# 11_Temp.net
KiCad netlist of a schematic drawn in Altium Designer
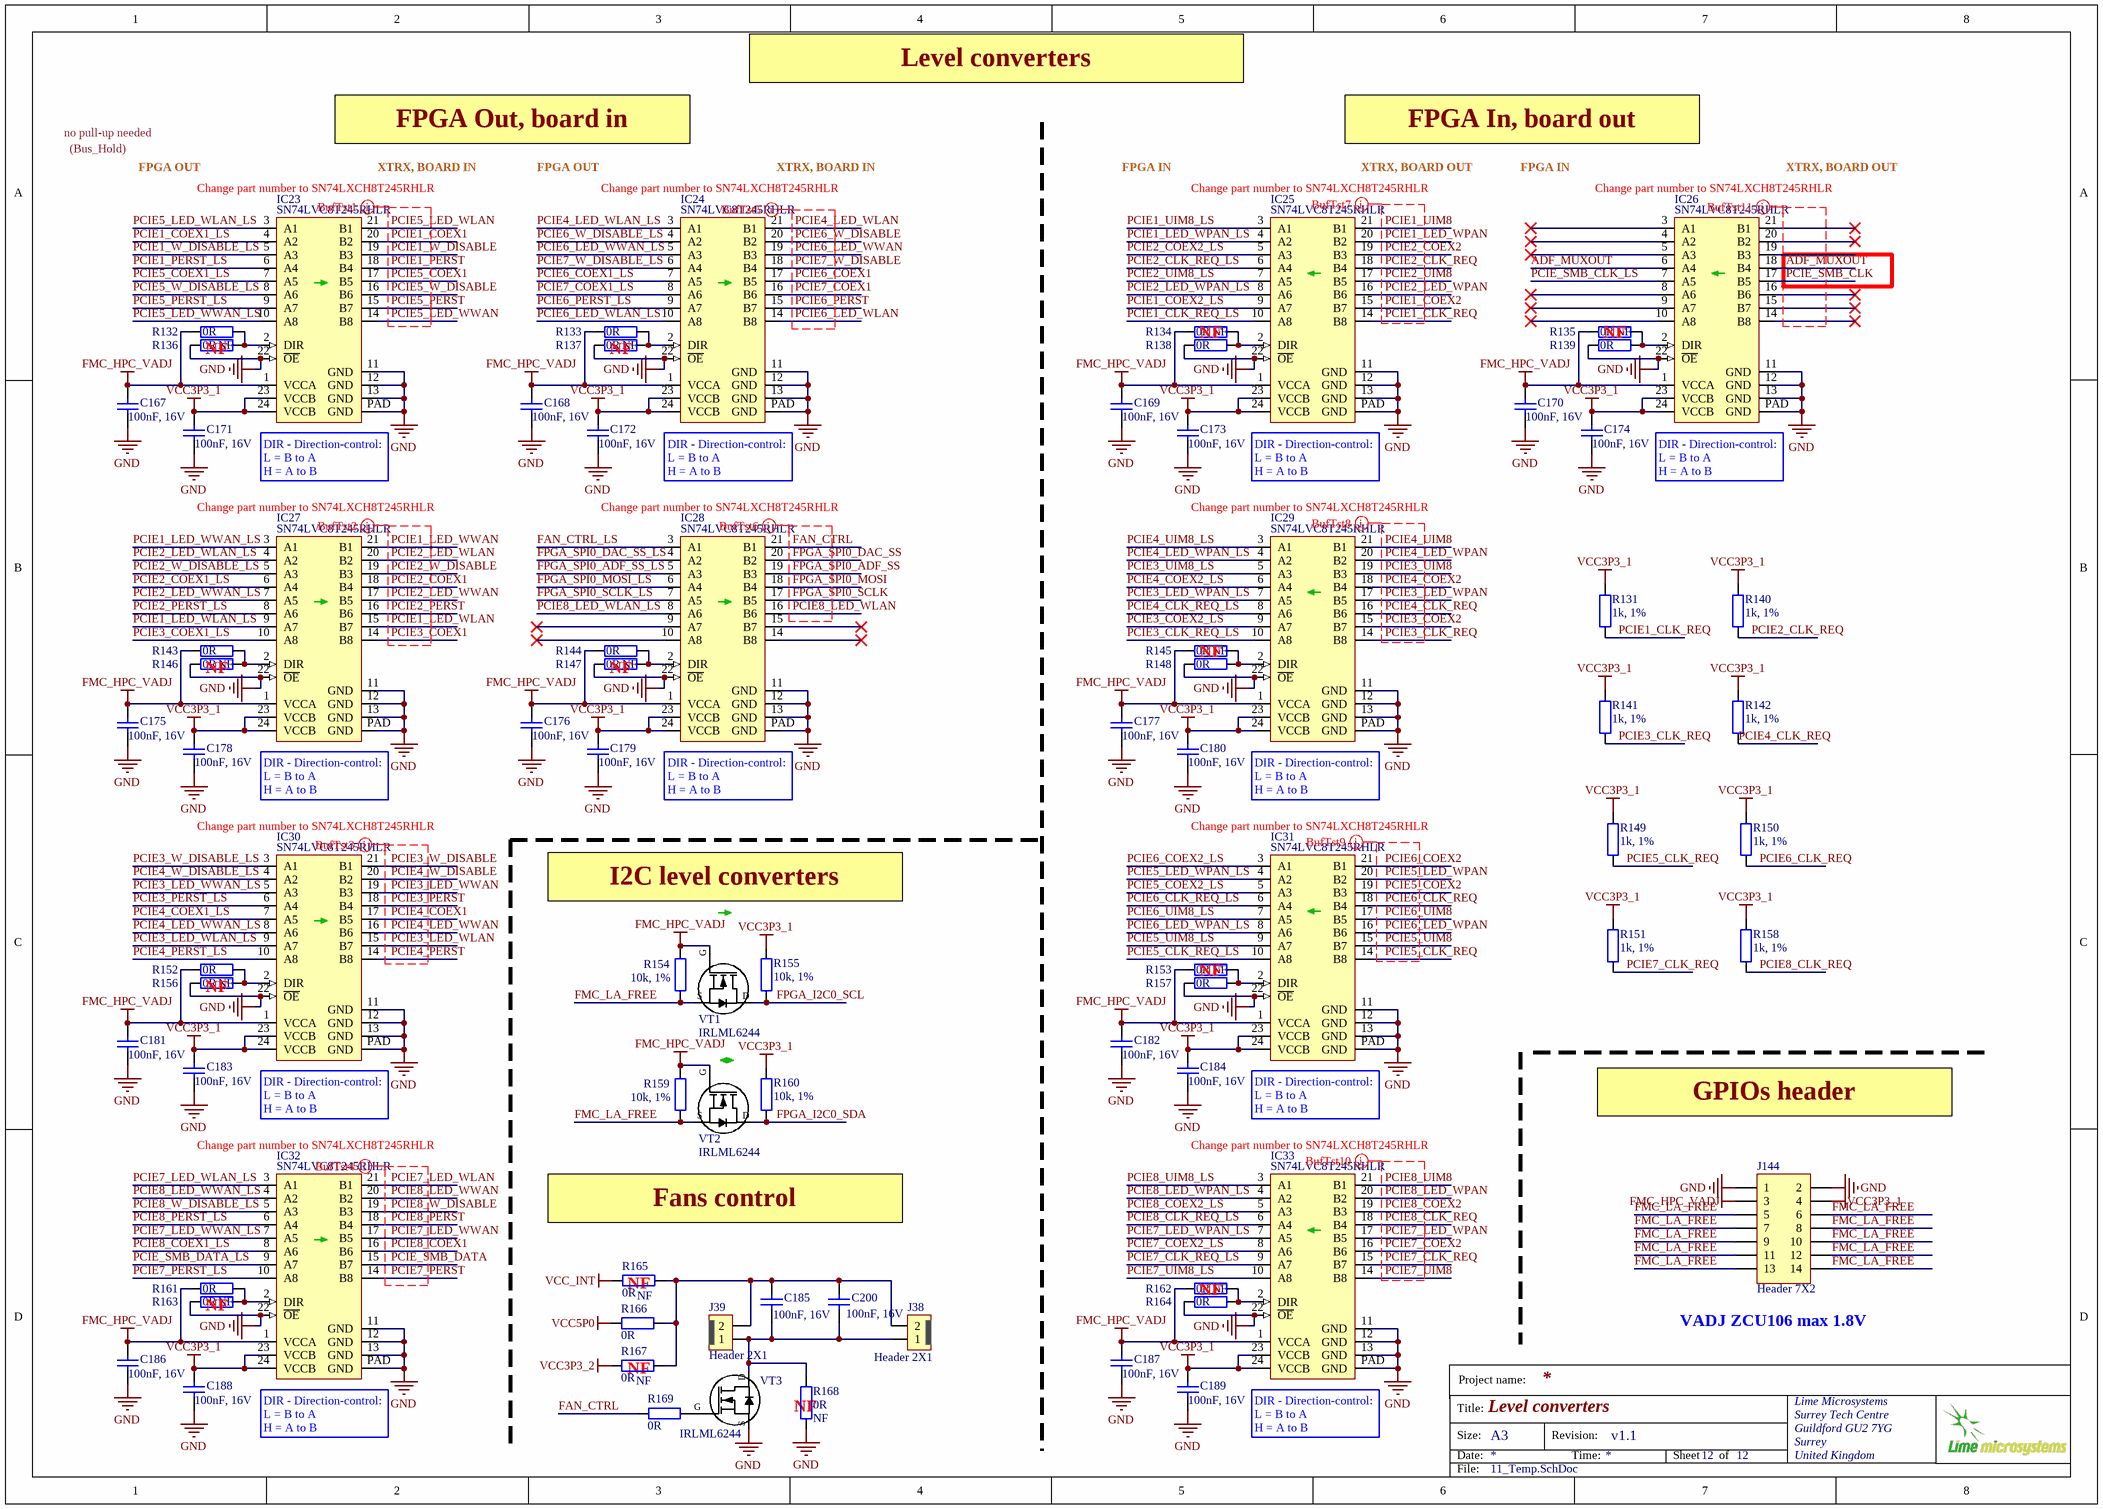
[diagram p0: 11_Temp.SchDoc]

(export (version "E")
  (design (tool "Eeschema 10.0.6"))
  (components
    (comp (ref "C167")
      (value "100nF, 16V")
      (footprint "CAP0402")
      (fields (field (name "TOLERANCE") "10 %") (field (name "MANUFACTURER") "Murata Electronics"))
      (libsource (lib "LimeFPGAboard_schLib") (part "Cap_0603"))
    )
    (comp (ref "C168")
      (value "100nF, 16V")
      (footprint "CAP0402")
      (fields (field (name "TOLERANCE") "10 %") (field (name "MANUFACTURER") "Murata Electronics"))
      (libsource (lib "LimeFPGAboard_schLib") (part "Cap_0603"))
    )
    (comp (ref "C169")
      (value "100nF, 16V")
      (footprint "CAP0402")
      (fields (field (name "TOLERANCE") "10 %") (field (name "MANUFACTURER") "Murata Electronics"))
      (libsource (lib "LimeFPGAboard_schLib") (part "Cap_0603"))
    )
    (comp (ref "C170")
      (value "100nF, 16V")
      (footprint "CAP0402")
      (fields (field (name "TOLERANCE") "10 %") (field (name "MANUFACTURER") "Murata Electronics"))
      (libsource (lib "LimeFPGAboard_schLib") (part "Cap_0603"))
    )
    (comp (ref "C171")
      (value "100nF, 16V")
      (footprint "CAP0402")
      (fields (field (name "TOLERANCE") "10 %") (field (name "MANUFACTURER") "Murata Electronics"))
      (libsource (lib "LimeFPGAboard_schLib") (part "Cap_0603"))
    )
    (comp (ref "C172")
      (value "100nF, 16V")
      (footprint "CAP0402")
      (fields (field (name "TOLERANCE") "10 %") (field (name "MANUFACTURER") "Murata Electronics"))
      (libsource (lib "LimeFPGAboard_schLib") (part "Cap_0603"))
    )
    (comp (ref "C173")
      (value "100nF, 16V")
      (footprint "CAP0402")
      (fields (field (name "TOLERANCE") "10 %") (field (name "MANUFACTURER") "Murata Electronics"))
      (libsource (lib "LimeFPGAboard_schLib") (part "Cap_0603"))
    )
    (comp (ref "C174")
      (value "100nF, 16V")
      (footprint "CAP0402")
      (fields (field (name "TOLERANCE") "10 %") (field (name "MANUFACTURER") "Murata Electronics"))
      (libsource (lib "LimeFPGAboard_schLib") (part "Cap_0603"))
    )
    (comp (ref "C175")
      (value "100nF, 16V")
      (footprint "CAP0402")
      (fields (field (name "TOLERANCE") "10 %") (field (name "MANUFACTURER") "Murata Electronics"))
      (libsource (lib "LimeFPGAboard_schLib") (part "Cap_0603"))
    )
    (comp (ref "C176")
      (value "100nF, 16V")
      (footprint "CAP0402")
      (fields (field (name "TOLERANCE") "10 %") (field (name "MANUFACTURER") "Murata Electronics"))
      (libsource (lib "LimeFPGAboard_schLib") (part "Cap_0603"))
    )
    (comp (ref "C177")
      (value "100nF, 16V")
      (footprint "CAP0402")
      (fields (field (name "TOLERANCE") "10 %") (field (name "MANUFACTURER") "Murata Electronics"))
      (libsource (lib "LimeFPGAboard_schLib") (part "Cap_0603"))
    )
    (comp (ref "C178")
      (value "100nF, 16V")
      (footprint "CAP0402")
      (fields (field (name "TOLERANCE") "10 %") (field (name "MANUFACTURER") "Murata Electronics"))
      (libsource (lib "LimeFPGAboard_schLib") (part "Cap_0603"))
    )
    (comp (ref "C179")
      (value "100nF, 16V")
      (footprint "CAP0402")
      (fields (field (name "TOLERANCE") "10 %") (field (name "MANUFACTURER") "Murata Electronics"))
      (libsource (lib "LimeFPGAboard_schLib") (part "Cap_0603"))
    )
    (comp (ref "C180")
      (value "100nF, 16V")
      (footprint "CAP0402")
      (fields (field (name "TOLERANCE") "10 %") (field (name "MANUFACTURER") "Murata Electronics"))
      (libsource (lib "LimeFPGAboard_schLib") (part "Cap_0603"))
    )
    (comp (ref "C181")
      (value "100nF, 16V")
      (footprint "CAP0402")
      (fields (field (name "TOLERANCE") "10 %") (field (name "MANUFACTURER") "Murata Electronics"))
      (libsource (lib "LimeFPGAboard_schLib") (part "Cap_0603"))
    )
    (comp (ref "C182")
      (value "100nF, 16V")
      (footprint "CAP0402")
      (fields (field (name "TOLERANCE") "10 %") (field (name "MANUFACTURER") "Murata Electronics"))
      (libsource (lib "LimeFPGAboard_schLib") (part "Cap_0603"))
    )
    (comp (ref "C183")
      (value "100nF, 16V")
      (footprint "CAP0402")
      (fields (field (name "TOLERANCE") "10 %") (field (name "MANUFACTURER") "Murata Electronics"))
      (libsource (lib "LimeFPGAboard_schLib") (part "Cap_0603"))
    )
    (comp (ref "C184")
      (value "100nF, 16V")
      (footprint "CAP0402")
      (fields (field (name "TOLERANCE") "10 %") (field (name "MANUFACTURER") "Murata Electronics"))
      (libsource (lib "LimeFPGAboard_schLib") (part "Cap_0603"))
    )
    (comp (ref "C185")
      (value "100nF, 16V")
      (footprint "CAP0402")
      (fields
        (field (name "TOLERANCE") "10 %")
        (field (name "MANUFACTURER") "Murata Electronics")
        (field (name "MANUFACTURER PART NUMBER") "GRM155R71C104KA88D")
      )
      (libsource (lib "") (part "Cap_0603_1"))
    )
    (comp (ref "C186")
      (value "100nF, 16V")
      (footprint "CAP0402")
      (fields (field (name "TOLERANCE") "10 %") (field (name "MANUFACTURER") "Murata Electronics"))
      (libsource (lib "LimeFPGAboard_schLib") (part "Cap_0603"))
    )
    (comp (ref "C187")
      (value "100nF, 16V")
      (footprint "CAP0402")
      (fields (field (name "TOLERANCE") "10 %") (field (name "MANUFACTURER") "Murata Electronics"))
      (libsource (lib "LimeFPGAboard_schLib") (part "Cap_0603"))
    )
    (comp (ref "C188")
      (value "100nF, 16V")
      (footprint "CAP0402")
      (fields (field (name "TOLERANCE") "10 %") (field (name "MANUFACTURER") "Murata Electronics"))
      (libsource (lib "LimeFPGAboard_schLib") (part "Cap_0603"))
    )
    (comp (ref "C189")
      (value "100nF, 16V")
      (footprint "CAP0402")
      (fields (field (name "TOLERANCE") "10 %") (field (name "MANUFACTURER") "Murata Electronics"))
      (libsource (lib "LimeFPGAboard_schLib") (part "Cap_0603"))
    )
    (comp (ref "C200")
      (value "100nF, 16V")
      (footprint "CAP0402")
      (fields
        (field (name "TOLERANCE") "10 %")
        (field (name "MANUFACTURER") "Murata Electronics")
        (field (name "MANUFACTURER PART NUMBER") "GRM155R71C104KA88D")
      )
      (libsource (lib "") (part "Cap_0603_1"))
    )
    (comp (ref "IC23")
      (value "SN74LVC8T245RHLR")
      (footprint "SN74LVC8T245RHLR_24-VQFN_LVL_SHIFTER")
      (fields (field (name "MANUFACTURER") "Texas Instruments"))
      (libsource (lib "*") (part "SN74LVC8T245RHLR_LVL_SHIFTER"))
    )
    (comp (ref "IC24")
      (value "SN74LVC8T245RHLR")
      (footprint "SN74LVC8T245RHLR_24-VQFN_LVL_SHIFTER")
      (fields (field (name "MANUFACTURER") "Texas Instruments"))
      (libsource (lib "*") (part "SN74LVC8T245RHLR_LVL_SHIFTER"))
    )
    (comp (ref "IC25")
      (value "SN74LVC8T245RHLR")
      (footprint "SN74LVC8T245RHLR_24-VQFN_LVL_SHIFTER")
      (fields (field (name "MANUFACTURER") "Texas Instruments"))
      (libsource (lib "*") (part "SN74LVC8T245RHLR_LVL_SHIFTER"))
    )
    (comp (ref "IC26")
      (value "SN74LVC8T245RHLR")
      (footprint "SN74LVC8T245RHLR_24-VQFN_LVL_SHIFTER")
      (fields (field (name "MANUFACTURER") "Texas Instruments"))
      (libsource (lib "*") (part "SN74LVC8T245RHLR_LVL_SHIFTER"))
    )
    (comp (ref "IC27")
      (value "SN74LVC8T245RHLR")
      (footprint "SN74LVC8T245RHLR_24-VQFN_LVL_SHIFTER")
      (fields (field (name "MANUFACTURER") "Texas Instruments"))
      (libsource (lib "*") (part "SN74LVC8T245RHLR_LVL_SHIFTER"))
    )
    (comp (ref "IC28")
      (value "SN74LVC8T245RHLR")
      (footprint "SN74LVC8T245RHLR_24-VQFN_LVL_SHIFTER")
      (fields (field (name "MANUFACTURER") "Texas Instruments"))
      (libsource (lib "*") (part "SN74LVC8T245RHLR_LVL_SHIFTER"))
    )
    (comp (ref "IC29")
      (value "SN74LVC8T245RHLR")
      (footprint "SN74LVC8T245RHLR_24-VQFN_LVL_SHIFTER")
      (fields (field (name "MANUFACTURER") "Texas Instruments"))
      (libsource (lib "*") (part "SN74LVC8T245RHLR_LVL_SHIFTER"))
    )
    (comp (ref "IC30")
      (value "SN74LVC8T245RHLR")
      (footprint "SN74LVC8T245RHLR_24-VQFN_LVL_SHIFTER")
      (fields (field (name "MANUFACTURER") "Texas Instruments"))
      (libsource (lib "*") (part "SN74LVC8T245RHLR_LVL_SHIFTER"))
    )
    (comp (ref "IC31")
      (value "SN74LVC8T245RHLR")
      (footprint "SN74LVC8T245RHLR_24-VQFN_LVL_SHIFTER")
      (fields (field (name "MANUFACTURER") "Texas Instruments"))
      (libsource (lib "*") (part "SN74LVC8T245RHLR_LVL_SHIFTER"))
    )
    (comp (ref "IC32")
      (value "SN74LVC8T245RHLR")
      (footprint "SN74LVC8T245RHLR_24-VQFN_LVL_SHIFTER")
      (fields (field (name "MANUFACTURER") "Texas Instruments"))
      (libsource (lib "*") (part "SN74LVC8T245RHLR_LVL_SHIFTER"))
    )
    (comp (ref "IC33")
      (value "SN74LVC8T245RHLR")
      (footprint "SN74LVC8T245RHLR_24-VQFN_LVL_SHIFTER")
      (fields (field (name "MANUFACTURER") "Texas Instruments"))
      (libsource (lib "*") (part "SN74LVC8T245RHLR_LVL_SHIFTER"))
    )
    (comp (ref "J38")
      (value "Header 2X1")
      (footprint "Header1x2_TH_LOCKING")
      (fields (field (name "MANUFACTURER PART NUMBER") "22-11-2026") (field (name "MANUFACTURER") "Molex"))
      (libsource (lib "LimeMicroAltiumLib_schLib_r04") (part "Header 2X1 LOCK"))
    )
    (comp (ref "J39")
      (value "Header 2X1")
      (footprint "Header1x2_TH_LOCKING")
      (fields (field (name "MANUFACTURER PART NUMBER") "22-11-2026") (field (name "MANUFACTURER") "Molex"))
      (libsource (lib "") (part "Header 2X1 LOCK_1"))
    )
    (comp (ref "J144")
      (value "Header 7X2")
      (footprint "Header7x2_TH")
      (description "Header, 7-Pin, Dual row")
      (fields
        (field (name "MANUFACTURER PART NUMBER") "PH2-14-UA")
        (field (name "MANUFACTURER") "Adam Equipment")
      )
      (libsource (lib "LimeMicroAltiumLib_schLib_r04") (part "Header 7X2"))
    )
    (comp (ref "R131")
      (value "1k, 1%")
      (footprint "RES0402")
      (fields (field (name "MANUFACTURER") "Stackpole Electronics Inc") (field (name "TOLERANCE") "±1%"))
      (libsource (lib "") (part "Res_0402_1"))
    )
    (comp (ref "R132")
      (value "0R")
      (footprint "RES0402")
      (fields (field (name "MANUFACTURER") "Yageo") (field (name "TOLERANCE") "Jumper"))
      (libsource (lib "LimeMicroAltiumLib_schLib") (part "Res_0402"))
    )
    (comp (ref "R133")
      (value "0R")
      (footprint "RES0402")
      (fields (field (name "MANUFACTURER") "Yageo") (field (name "TOLERANCE") "Jumper"))
      (libsource (lib "LimeMicroAltiumLib_schLib") (part "Res_0402"))
    )
    (comp (ref "R134")
      (value "0R")
      (footprint "RES0402")
      (fields
        (field (name "ASSEMBLY INFO") "NF")
        (field (name "MANUFACTURER") "Yageo")
        (field (name "TOLERANCE") "Jumper")
      )
      (libsource (lib "LimeMicroAltiumLib_schLib") (part "Res_0402"))
    )
    (comp (ref "R135")
      (value "0R")
      (footprint "RES0402")
      (fields
        (field (name "ASSEMBLY INFO") "NF")
        (field (name "MANUFACTURER") "Yageo")
        (field (name "TOLERANCE") "Jumper")
      )
      (libsource (lib "LimeMicroAltiumLib_schLib") (part "Res_0402"))
    )
    (comp (ref "R136")
      (value "0R")
      (footprint "RES0402")
      (fields
        (field (name "ASSEMBLY INFO") "NF")
        (field (name "MANUFACTURER") "Yageo")
        (field (name "TOLERANCE") "Jumper")
      )
      (libsource (lib "LimeMicroAltiumLib_schLib") (part "Res_0402"))
    )
    (comp (ref "R137")
      (value "0R")
      (footprint "RES0402")
      (fields
        (field (name "ASSEMBLY INFO") "NF")
        (field (name "MANUFACTURER") "Yageo")
        (field (name "TOLERANCE") "Jumper")
      )
      (libsource (lib "LimeMicroAltiumLib_schLib") (part "Res_0402"))
    )
    (comp (ref "R138")
      (value "0R")
      (footprint "RES0402")
      (fields (field (name "MANUFACTURER") "Yageo") (field (name "TOLERANCE") "Jumper"))
      (libsource (lib "LimeMicroAltiumLib_schLib") (part "Res_0402"))
    )
    (comp (ref "R139")
      (value "0R")
      (footprint "RES0402")
      (fields (field (name "MANUFACTURER") "Yageo") (field (name "TOLERANCE") "Jumper"))
      (libsource (lib "LimeMicroAltiumLib_schLib") (part "Res_0402"))
    )
    (comp (ref "R140")
      (value "1k, 1%")
      (footprint "RES0402")
      (fields (field (name "MANUFACTURER") "Stackpole Electronics Inc") (field (name "TOLERANCE") "±1%"))
      (libsource (lib "") (part "Res_0402_1"))
    )
    (comp (ref "R141")
      (value "1k, 1%")
      (footprint "RES0402")
      (fields (field (name "MANUFACTURER") "Stackpole Electronics Inc") (field (name "TOLERANCE") "±1%"))
      (libsource (lib "") (part "Res_0402_1"))
    )
    (comp (ref "R142")
      (value "1k, 1%")
      (footprint "RES0402")
      (fields (field (name "MANUFACTURER") "Stackpole Electronics Inc") (field (name "TOLERANCE") "±1%"))
      (libsource (lib "") (part "Res_0402_1"))
    )
    (comp (ref "R143")
      (value "0R")
      (footprint "RES0402")
      (fields (field (name "MANUFACTURER") "Yageo") (field (name "TOLERANCE") "Jumper"))
      (libsource (lib "LimeMicroAltiumLib_schLib") (part "Res_0402"))
    )
    (comp (ref "R144")
      (value "0R")
      (footprint "RES0402")
      (fields (field (name "MANUFACTURER") "Yageo") (field (name "TOLERANCE") "Jumper"))
      (libsource (lib "LimeMicroAltiumLib_schLib") (part "Res_0402"))
    )
    (comp (ref "R145")
      (value "0R")
      (footprint "RES0402")
      (fields
        (field (name "ASSEMBLY INFO") "NF")
        (field (name "MANUFACTURER") "Yageo")
        (field (name "TOLERANCE") "Jumper")
      )
      (libsource (lib "LimeMicroAltiumLib_schLib") (part "Res_0402"))
    )
    (comp (ref "R146")
      (value "0R")
      (footprint "RES0402")
      (fields
        (field (name "ASSEMBLY INFO") "NF")
        (field (name "MANUFACTURER") "Yageo")
        (field (name "TOLERANCE") "Jumper")
      )
      (libsource (lib "LimeMicroAltiumLib_schLib") (part "Res_0402"))
    )
    (comp (ref "R147")
      (value "0R")
      (footprint "RES0402")
      (fields
        (field (name "ASSEMBLY INFO") "NF")
        (field (name "MANUFACTURER") "Yageo")
        (field (name "TOLERANCE") "Jumper")
      )
      (libsource (lib "LimeMicroAltiumLib_schLib") (part "Res_0402"))
    )
    (comp (ref "R148")
      (value "0R")
      (footprint "RES0402")
      (fields (field (name "MANUFACTURER") "Yageo") (field (name "TOLERANCE") "Jumper"))
      (libsource (lib "LimeMicroAltiumLib_schLib") (part "Res_0402"))
    )
    (comp (ref "R149")
      (value "1k, 1%")
      (footprint "RES0402")
      (fields (field (name "MANUFACTURER") "Stackpole Electronics Inc") (field (name "TOLERANCE") "±1%"))
      (libsource (lib "") (part "Res_0402_1"))
    )
    (comp (ref "R150")
      (value "1k, 1%")
      (footprint "RES0402")
      (fields (field (name "MANUFACTURER") "Stackpole Electronics Inc") (field (name "TOLERANCE") "±1%"))
      (libsource (lib "") (part "Res_0402_1"))
    )
    (comp (ref "R151")
      (value "1k, 1%")
      (footprint "RES0402")
      (fields (field (name "MANUFACTURER") "Stackpole Electronics Inc") (field (name "TOLERANCE") "±1%"))
      (libsource (lib "") (part "Res_0402_1"))
    )
    (comp (ref "R152")
      (value "0R")
      (footprint "RES0402")
      (fields (field (name "MANUFACTURER") "Yageo") (field (name "TOLERANCE") "Jumper"))
      (libsource (lib "LimeMicroAltiumLib_schLib") (part "Res_0402"))
    )
    (comp (ref "R153")
      (value "0R")
      (footprint "RES0402")
      (fields
        (field (name "ASSEMBLY INFO") "NF")
        (field (name "MANUFACTURER") "Yageo")
        (field (name "TOLERANCE") "Jumper")
      )
      (libsource (lib "LimeMicroAltiumLib_schLib") (part "Res_0402"))
    )
    (comp (ref "R154")
      (value "10k, 1%")
      (footprint "RES0402")
      (fields (field (name "MANUFACTURER") "Yageo") (field (name "TOLERANCE") "±1%"))
      (libsource (lib "") (part "Res_0402_1"))
    )
    (comp (ref "R155")
      (value "10k, 1%")
      (footprint "RES0402")
      (fields (field (name "MANUFACTURER") "Yageo") (field (name "TOLERANCE") "±1%"))
      (libsource (lib "") (part "Res_0402_1"))
    )
    (comp (ref "R156")
      (value "0R")
      (footprint "RES0402")
      (fields
        (field (name "ASSEMBLY INFO") "NF")
        (field (name "MANUFACTURER") "Yageo")
        (field (name "TOLERANCE") "Jumper")
      )
      (libsource (lib "LimeMicroAltiumLib_schLib") (part "Res_0402"))
    )
    (comp (ref "R157")
      (value "0R")
      (footprint "RES0402")
      (fields (field (name "MANUFACTURER") "Yageo") (field (name "TOLERANCE") "Jumper"))
      (libsource (lib "LimeMicroAltiumLib_schLib") (part "Res_0402"))
    )
    (comp (ref "R158")
      (value "1k, 1%")
      (footprint "RES0402")
      (fields (field (name "MANUFACTURER") "Stackpole Electronics Inc") (field (name "TOLERANCE") "±1%"))
      (libsource (lib "") (part "Res_0402_1"))
    )
    (comp (ref "R159")
      (value "10k, 1%")
      (footprint "RES0402")
      (fields (field (name "MANUFACTURER") "Yageo") (field (name "TOLERANCE") "±1%"))
      (libsource (lib "") (part "Res_0402_1"))
    )
    (comp (ref "R160")
      (value "10k, 1%")
      (footprint "RES0402")
      (fields (field (name "MANUFACTURER") "Yageo") (field (name "TOLERANCE") "±1%"))
      (libsource (lib "") (part "Res_0402_1"))
    )
    (comp (ref "R161")
      (value "0R")
      (footprint "RES0402")
      (fields (field (name "MANUFACTURER") "Yageo") (field (name "TOLERANCE") "Jumper"))
      (libsource (lib "LimeMicroAltiumLib_schLib") (part "Res_0402"))
    )
    (comp (ref "R162")
      (value "0R")
      (footprint "RES0402")
      (fields
        (field (name "ASSEMBLY INFO") "NF")
        (field (name "MANUFACTURER") "Yageo")
        (field (name "TOLERANCE") "Jumper")
      )
      (libsource (lib "LimeMicroAltiumLib_schLib") (part "Res_0402"))
    )
    (comp (ref "R163")
      (value "0R")
      (footprint "RES0402")
      (fields
        (field (name "ASSEMBLY INFO") "NF")
        (field (name "MANUFACTURER") "Yageo")
        (field (name "TOLERANCE") "Jumper")
      )
      (libsource (lib "LimeMicroAltiumLib_schLib") (part "Res_0402"))
    )
    (comp (ref "R164")
      (value "0R")
      (footprint "RES0402")
      (fields (field (name "MANUFACTURER") "Yageo") (field (name "TOLERANCE") "Jumper"))
      (libsource (lib "LimeMicroAltiumLib_schLib") (part "Res_0402"))
    )
    (comp (ref "R165")
      (value "0R")
      (footprint "RES0402")
      (fields
        (field (name "ASSEMBLY INFO") "NF")
        (field (name "MANUFACTURER") "Yageo")
        (field (name "TOLERANCE") "Jumper")
      )
      (libsource (lib "") (part "Res_0402_1"))
    )
    (comp (ref "R166")
      (value "0R")
      (footprint "RES0402")
      (fields (field (name "MANUFACTURER") "Yageo") (field (name "TOLERANCE") "Jumper"))
      (libsource (lib "") (part "Res_0402_1"))
    )
    (comp (ref "R167")
      (value "0R")
      (footprint "RES0402")
      (fields
        (field (name "ASSEMBLY INFO") "NF")
        (field (name "MANUFACTURER") "Yageo")
        (field (name "TOLERANCE") "Jumper")
      )
      (libsource (lib "") (part "Res_0402_1"))
    )
    (comp (ref "R168")
      (value "0R")
      (footprint "RES0402")
      (fields
        (field (name "ASSEMBLY INFO") "NF")
        (field (name "MANUFACTURER") "Yageo")
        (field (name "TOLERANCE") "Jumper")
      )
      (libsource (lib "") (part "Res_0402_1"))
    )
    (comp (ref "R169")
      (value "0R")
      (footprint "RES0402")
      (fields (field (name "MANUFACTURER") "Yageo") (field (name "TOLERANCE") "Jumper"))
      (libsource (lib "") (part "Res_0402_1"))
    )
    (comp (ref "VT1")
      (value "IRLML6244")
      (footprint "SOT23-3")
      (description "NDS331N")
      (fields (field (name "MANUFACTURER") "Infineon Technologies"))
      (libsource (lib "LimeFPGAboard_schLib") (part "NDS331N"))
    )
    (comp (ref "VT2")
      (value "IRLML6244")
      (footprint "SOT23-3")
      (description "NDS331N")
      (fields (field (name "MANUFACTURER") "Infineon Technologies"))
      (libsource (lib "LimeFPGAboard_schLib") (part "NDS331N"))
    )
    (comp (ref "VT3")
      (value "IRLML6244")
      (footprint "SOT23-3")
      (description "NDS331N")
      (fields (field (name "MANUFACTURER") "Infineon Technologies"))
      (libsource (lib "LimeFPGAboard_schLib") (part "NDS331N"))
    )
  )
  (nets
    (net (code "1") (name "/ADF_MUXOUT") (class "Default")
      (node (ref "IC26") (pin "18") (pinfunction "B4_18") (pintype "bidirectional"))
      (node (ref "IC26") (pin "6") (pinfunction "A4_6") (pintype "bidirectional"))
    )
    (net (code "2") (name "/FAN_CTRL") (class "Default")
      (node (ref "IC28") (pin "21") (pinfunction "B1_21") (pintype "bidirectional"))
      (node (ref "R169") (pin "1") (pinfunction "1_1") (pintype "passive"))
    )
    (net (code "3") (name "/FAN_CTRL_LS") (class "Default")
      (node (ref "IC28") (pin "3") (pinfunction "A1_3") (pintype "bidirectional"))
    )
    (net (code "4") (name "/FMC_LA_FREE") (class "Default")
      (node (ref "J144") (pin "10") (pinfunction "10_10") (pintype "passive"))
      (node (ref "J144") (pin "11") (pinfunction "11_11") (pintype "passive"))
      (node (ref "J144") (pin "12") (pinfunction "12_12") (pintype "passive"))
      (node (ref "J144") (pin "13") (pinfunction "13_13") (pintype "passive"))
      (node (ref "J144") (pin "14") (pinfunction "14_14") (pintype "passive"))
      (node (ref "J144") (pin "5") (pinfunction "5_5") (pintype "passive"))
      (node (ref "J144") (pin "6") (pinfunction "6_6") (pintype "passive"))
      (node (ref "J144") (pin "7") (pinfunction "7_7") (pintype "passive"))
      (node (ref "J144") (pin "8") (pinfunction "8_8") (pintype "passive"))
      (node (ref "J144") (pin "9") (pinfunction "9_9") (pintype "passive"))
      (node (ref "R154") (pin "2") (pinfunction "2_2") (pintype "passive"))
      (node (ref "R159") (pin "2") (pinfunction "2_2") (pintype "passive"))
      (node (ref "VT1") (pin "S") (pinfunction "S_S") (pintype "passive"))
      (node (ref "VT2") (pin "S") (pinfunction "S_S") (pintype "passive"))
    )
    (net (code "5") (name "/FPGA_I2C0_SCL") (class "Default")
      (node (ref "R155") (pin "2") (pinfunction "2_2") (pintype "passive"))
      (node (ref "VT1") (pin "D") (pinfunction "D_D") (pintype "passive"))
    )
    (net (code "6") (name "/FPGA_I2C0_SDA") (class "Default")
      (node (ref "R160") (pin "2") (pinfunction "2_2") (pintype "passive"))
      (node (ref "VT2") (pin "D") (pinfunction "D_D") (pintype "passive"))
    )
    (net (code "7") (name "/FPGA_SPI0_ADF_SS") (class "Default")
      (node (ref "IC28") (pin "19") (pinfunction "B3_19") (pintype "bidirectional"))
    )
    (net (code "8") (name "/FPGA_SPI0_ADF_SS_LS") (class "Default")
      (node (ref "IC28") (pin "5") (pinfunction "A3_5") (pintype "bidirectional"))
    )
    (net (code "9") (name "/FPGA_SPI0_DAC_SS") (class "Default")
      (node (ref "IC28") (pin "20") (pinfunction "B2_20") (pintype "bidirectional"))
    )
    (net (code "10") (name "/FPGA_SPI0_DAC_SS_LS") (class "Default")
      (node (ref "IC28") (pin "4") (pinfunction "A2_4") (pintype "bidirectional"))
    )
    (net (code "11") (name "/FPGA_SPI0_MOSI") (class "Default")
      (node (ref "IC28") (pin "18") (pinfunction "B4_18") (pintype "bidirectional"))
    )
    (net (code "12") (name "/FPGA_SPI0_MOSI_LS") (class "Default")
      (node (ref "IC28") (pin "6") (pinfunction "A4_6") (pintype "bidirectional"))
    )
    (net (code "13") (name "/FPGA_SPI0_SCLK") (class "Default")
      (node (ref "IC28") (pin "17") (pinfunction "B5_17") (pintype "bidirectional"))
    )
    (net (code "14") (name "/FPGA_SPI0_SCLK_LS") (class "Default")
      (node (ref "IC28") (pin "7") (pinfunction "A5_7") (pintype "bidirectional"))
    )
    (net (code "15") (name "/PCIE1_CLK_REQ") (class "Default")
      (node (ref "IC25") (pin "14") (pinfunction "B8_14") (pintype "bidirectional"))
      (node (ref "R131") (pin "1") (pinfunction "1_1") (pintype "passive"))
    )
    (net (code "16") (name "/PCIE1_CLK_REQ_LS") (class "Default")
      (node (ref "IC25") (pin "10") (pinfunction "A8_10") (pintype "bidirectional"))
    )
    (net (code "17") (name "/PCIE1_COEX1") (class "Default")
      (node (ref "IC23") (pin "20") (pinfunction "B2_20") (pintype "bidirectional"))
    )
    (net (code "18") (name "/PCIE1_COEX1_LS") (class "Default")
      (node (ref "IC23") (pin "4") (pinfunction "A2_4") (pintype "bidirectional"))
    )
    (net (code "19") (name "/PCIE1_COEX2") (class "Default")
      (node (ref "IC25") (pin "15") (pinfunction "B7_15") (pintype "bidirectional"))
    )
    (net (code "20") (name "/PCIE1_COEX2_LS") (class "Default")
      (node (ref "IC25") (pin "9") (pinfunction "A7_9") (pintype "bidirectional"))
    )
    (net (code "21") (name "/PCIE1_LED_WLAN") (class "Default")
      (node (ref "IC27") (pin "15") (pinfunction "B7_15") (pintype "bidirectional"))
    )
    (net (code "22") (name "/PCIE1_LED_WLAN_LS") (class "Default")
      (node (ref "IC27") (pin "9") (pinfunction "A7_9") (pintype "bidirectional"))
    )
    (net (code "23") (name "/PCIE1_LED_WPAN") (class "Default")
      (node (ref "IC25") (pin "20") (pinfunction "B2_20") (pintype "bidirectional"))
    )
    (net (code "24") (name "/PCIE1_LED_WPAN_LS") (class "Default")
      (node (ref "IC25") (pin "4") (pinfunction "A2_4") (pintype "bidirectional"))
    )
    (net (code "25") (name "/PCIE1_LED_WWAN") (class "Default")
      (node (ref "IC27") (pin "21") (pinfunction "B1_21") (pintype "bidirectional"))
    )
    (net (code "26") (name "/PCIE1_LED_WWAN_LS") (class "Default")
      (node (ref "IC27") (pin "3") (pinfunction "A1_3") (pintype "bidirectional"))
    )
    (net (code "27") (name "/PCIE1_PERST") (class "Default")
      (node (ref "IC23") (pin "18") (pinfunction "B4_18") (pintype "bidirectional"))
    )
    (net (code "28") (name "/PCIE1_PERST_LS") (class "Default")
      (node (ref "IC23") (pin "6") (pinfunction "A4_6") (pintype "bidirectional"))
    )
    (net (code "29") (name "/PCIE1_UIM8") (class "Default")
      (node (ref "IC25") (pin "21") (pinfunction "B1_21") (pintype "bidirectional"))
    )
    (net (code "30") (name "/PCIE1_UIM8_LS") (class "Default")
      (node (ref "IC25") (pin "3") (pinfunction "A1_3") (pintype "bidirectional"))
    )
    (net (code "31") (name "/PCIE1_W_DISABLE") (class "Default")
      (node (ref "IC23") (pin "19") (pinfunction "B3_19") (pintype "bidirectional"))
    )
    (net (code "32") (name "/PCIE1_W_DISABLE_LS") (class "Default")
      (node (ref "IC23") (pin "5") (pinfunction "A3_5") (pintype "bidirectional"))
    )
    (net (code "33") (name "/PCIE2_CLK_REQ") (class "Default")
      (node (ref "IC25") (pin "18") (pinfunction "B4_18") (pintype "bidirectional"))
      (node (ref "R140") (pin "1") (pinfunction "1_1") (pintype "passive"))
    )
    (net (code "34") (name "/PCIE2_CLK_REQ_LS") (class "Default")
      (node (ref "IC25") (pin "6") (pinfunction "A4_6") (pintype "bidirectional"))
    )
    (net (code "35") (name "/PCIE2_COEX1") (class "Default")
      (node (ref "IC27") (pin "18") (pinfunction "B4_18") (pintype "bidirectional"))
    )
    (net (code "36") (name "/PCIE2_COEX1_LS") (class "Default")
      (node (ref "IC27") (pin "6") (pinfunction "A4_6") (pintype "bidirectional"))
    )
    (net (code "37") (name "/PCIE2_COEX2") (class "Default")
      (node (ref "IC25") (pin "19") (pinfunction "B3_19") (pintype "bidirectional"))
    )
    (net (code "38") (name "/PCIE2_COEX2_LS") (class "Default")
      (node (ref "IC25") (pin "5") (pinfunction "A3_5") (pintype "bidirectional"))
    )
    (net (code "39") (name "/PCIE2_LED_WLAN") (class "Default")
      (node (ref "IC27") (pin "20") (pinfunction "B2_20") (pintype "bidirectional"))
    )
    (net (code "40") (name "/PCIE2_LED_WLAN_LS") (class "Default")
      (node (ref "IC27") (pin "4") (pinfunction "A2_4") (pintype "bidirectional"))
    )
    (net (code "41") (name "/PCIE2_LED_WPAN") (class "Default")
      (node (ref "IC25") (pin "16") (pinfunction "B6_16") (pintype "bidirectional"))
    )
    (net (code "42") (name "/PCIE2_LED_WPAN_LS") (class "Default")
      (node (ref "IC25") (pin "8") (pinfunction "A6_8") (pintype "bidirectional"))
    )
    (net (code "43") (name "/PCIE2_LED_WWAN") (class "Default")
      (node (ref "IC27") (pin "17") (pinfunction "B5_17") (pintype "bidirectional"))
    )
    (net (code "44") (name "/PCIE2_LED_WWAN_LS") (class "Default")
      (node (ref "IC27") (pin "7") (pinfunction "A5_7") (pintype "bidirectional"))
    )
    (net (code "45") (name "/PCIE2_PERST") (class "Default")
      (node (ref "IC27") (pin "16") (pinfunction "B6_16") (pintype "bidirectional"))
    )
    (net (code "46") (name "/PCIE2_PERST_LS") (class "Default")
      (node (ref "IC27") (pin "8") (pinfunction "A6_8") (pintype "bidirectional"))
    )
    (net (code "47") (name "/PCIE2_UIM8") (class "Default")
      (node (ref "IC25") (pin "17") (pinfunction "B5_17") (pintype "bidirectional"))
    )
    (net (code "48") (name "/PCIE2_UIM8_LS") (class "Default")
      (node (ref "IC25") (pin "7") (pinfunction "A5_7") (pintype "bidirectional"))
    )
    (net (code "49") (name "/PCIE2_W_DISABLE") (class "Default")
      (node (ref "IC27") (pin "19") (pinfunction "B3_19") (pintype "bidirectional"))
    )
    (net (code "50") (name "/PCIE2_W_DISABLE_LS") (class "Default")
      (node (ref "IC27") (pin "5") (pinfunction "A3_5") (pintype "bidirectional"))
    )
    (net (code "51") (name "/PCIE3_CLK_REQ") (class "Default")
      (node (ref "IC29") (pin "14") (pinfunction "B8_14") (pintype "bidirectional"))
      (node (ref "R141") (pin "1") (pinfunction "1_1") (pintype "passive"))
    )
    (net (code "52") (name "/PCIE3_CLK_REQ_LS") (class "Default")
      (node (ref "IC29") (pin "10") (pinfunction "A8_10") (pintype "bidirectional"))
    )
    (net (code "53") (name "/PCIE3_COEX1") (class "Default")
      (node (ref "IC27") (pin "14") (pinfunction "B8_14") (pintype "bidirectional"))
    )
    (net (code "54") (name "/PCIE3_COEX1_LS") (class "Default")
      (node (ref "IC27") (pin "10") (pinfunction "A8_10") (pintype "bidirectional"))
    )
    (net (code "55") (name "/PCIE3_COEX2") (class "Default")
      (node (ref "IC29") (pin "15") (pinfunction "B7_15") (pintype "bidirectional"))
    )
    (net (code "56") (name "/PCIE3_COEX2_LS") (class "Default")
      (node (ref "IC29") (pin "9") (pinfunction "A7_9") (pintype "bidirectional"))
    )
    (net (code "57") (name "/PCIE3_LED_WLAN") (class "Default")
      (node (ref "IC30") (pin "15") (pinfunction "B7_15") (pintype "bidirectional"))
    )
    (net (code "58") (name "/PCIE3_LED_WLAN_LS") (class "Default")
      (node (ref "IC30") (pin "9") (pinfunction "A7_9") (pintype "bidirectional"))
    )
    (net (code "59") (name "/PCIE3_LED_WPAN") (class "Default")
      (node (ref "IC29") (pin "17") (pinfunction "B5_17") (pintype "bidirectional"))
    )
    (net (code "60") (name "/PCIE3_LED_WPAN_LS") (class "Default")
      (node (ref "IC29") (pin "7") (pinfunction "A5_7") (pintype "bidirectional"))
    )
    (net (code "61") (name "/PCIE3_LED_WWAN") (class "Default")
      (node (ref "IC30") (pin "19") (pinfunction "B3_19") (pintype "bidirectional"))
    )
    (net (code "62") (name "/PCIE3_LED_WWAN_LS") (class "Default")
      (node (ref "IC30") (pin "5") (pinfunction "A3_5") (pintype "bidirectional"))
    )
    (net (code "63") (name "/PCIE3_PERST") (class "Default")
      (node (ref "IC30") (pin "18") (pinfunction "B4_18") (pintype "bidirectional"))
    )
    (net (code "64") (name "/PCIE3_PERST_LS") (class "Default")
      (node (ref "IC30") (pin "6") (pinfunction "A4_6") (pintype "bidirectional"))
    )
    (net (code "65") (name "/PCIE3_UIM8") (class "Default")
      (node (ref "IC29") (pin "19") (pinfunction "B3_19") (pintype "bidirectional"))
    )
    (net (code "66") (name "/PCIE3_UIM8_LS") (class "Default")
      (node (ref "IC29") (pin "5") (pinfunction "A3_5") (pintype "bidirectional"))
    )
    (net (code "67") (name "/PCIE3_W_DISABLE") (class "Default")
      (node (ref "IC30") (pin "21") (pinfunction "B1_21") (pintype "bidirectional"))
    )
    (net (code "68") (name "/PCIE3_W_DISABLE_LS") (class "Default")
      (node (ref "IC30") (pin "3") (pinfunction "A1_3") (pintype "bidirectional"))
    )
    (net (code "69") (name "/PCIE4_CLK_REQ") (class "Default")
      (node (ref "IC29") (pin "16") (pinfunction "B6_16") (pintype "bidirectional"))
      (node (ref "R142") (pin "1") (pinfunction "1_1") (pintype "passive"))
    )
    (net (code "70") (name "/PCIE4_CLK_REQ_LS") (class "Default")
      (node (ref "IC29") (pin "8") (pinfunction "A6_8") (pintype "bidirectional"))
    )
    (net (code "71") (name "/PCIE4_COEX1") (class "Default")
      (node (ref "IC30") (pin "17") (pinfunction "B5_17") (pintype "bidirectional"))
    )
    (net (code "72") (name "/PCIE4_COEX1_LS") (class "Default")
      (node (ref "IC30") (pin "7") (pinfunction "A5_7") (pintype "bidirectional"))
    )
    (net (code "73") (name "/PCIE4_COEX2") (class "Default")
      (node (ref "IC29") (pin "18") (pinfunction "B4_18") (pintype "bidirectional"))
    )
    (net (code "74") (name "/PCIE4_COEX2_LS") (class "Default")
      (node (ref "IC29") (pin "6") (pinfunction "A4_6") (pintype "bidirectional"))
    )
    (net (code "75") (name "/PCIE4_LED_WLAN") (class "Default")
      (node (ref "IC24") (pin "21") (pinfunction "B1_21") (pintype "bidirectional"))
    )
    (net (code "76") (name "/PCIE4_LED_WLAN_LS") (class "Default")
      (node (ref "IC24") (pin "3") (pinfunction "A1_3") (pintype "bidirectional"))
    )
    (net (code "77") (name "/PCIE4_LED_WPAN") (class "Default")
      (node (ref "IC29") (pin "20") (pinfunction "B2_20") (pintype "bidirectional"))
    )
    (net (code "78") (name "/PCIE4_LED_WPAN_LS") (class "Default")
      (node (ref "IC29") (pin "4") (pinfunction "A2_4") (pintype "bidirectional"))
    )
    (net (code "79") (name "/PCIE4_LED_WWAN") (class "Default")
      (node (ref "IC30") (pin "16") (pinfunction "B6_16") (pintype "bidirectional"))
    )
    (net (code "80") (name "/PCIE4_LED_WWAN_LS") (class "Default")
      (node (ref "IC30") (pin "8") (pinfunction "A6_8") (pintype "bidirectional"))
    )
    (net (code "81") (name "/PCIE4_PERST") (class "Default")
      (node (ref "IC30") (pin "14") (pinfunction "B8_14") (pintype "bidirectional"))
    )
    (net (code "82") (name "/PCIE4_PERST_LS") (class "Default")
      (node (ref "IC30") (pin "10") (pinfunction "A8_10") (pintype "bidirectional"))
    )
    (net (code "83") (name "/PCIE4_UIM8") (class "Default")
      (node (ref "IC29") (pin "21") (pinfunction "B1_21") (pintype "bidirectional"))
    )
    (net (code "84") (name "/PCIE4_UIM8_LS") (class "Default")
      (node (ref "IC29") (pin "3") (pinfunction "A1_3") (pintype "bidirectional"))
    )
    (net (code "85") (name "/PCIE4_W_DISABLE") (class "Default")
      (node (ref "IC30") (pin "20") (pinfunction "B2_20") (pintype "bidirectional"))
    )
    (net (code "86") (name "/PCIE4_W_DISABLE_LS") (class "Default")
      (node (ref "IC30") (pin "4") (pinfunction "A2_4") (pintype "bidirectional"))
    )
    (net (code "87") (name "/PCIE5_CLK_REQ") (class "Default")
      (node (ref "IC31") (pin "14") (pinfunction "B8_14") (pintype "bidirectional"))
      (node (ref "R149") (pin "1") (pinfunction "1_1") (pintype "passive"))
    )
    (net (code "88") (name "/PCIE5_CLK_REQ_LS") (class "Default")
      (node (ref "IC31") (pin "10") (pinfunction "A8_10") (pintype "bidirectional"))
    )
    (net (code "89") (name "/PCIE5_COEX1") (class "Default")
      (node (ref "IC23") (pin "17") (pinfunction "B5_17") (pintype "bidirectional"))
    )
    (net (code "90") (name "/PCIE5_COEX1_LS") (class "Default")
      (node (ref "IC23") (pin "7") (pinfunction "A5_7") (pintype "bidirectional"))
    )
    (net (code "91") (name "/PCIE5_COEX2") (class "Default")
      (node (ref "IC31") (pin "19") (pinfunction "B3_19") (pintype "bidirectional"))
    )
    (net (code "92") (name "/PCIE5_COEX2_LS") (class "Default")
      (node (ref "IC31") (pin "5") (pinfunction "A3_5") (pintype "bidirectional"))
    )
    (net (code "93") (name "/PCIE5_LED_WLAN") (class "Default")
      (node (ref "IC23") (pin "21") (pinfunction "B1_21") (pintype "bidirectional"))
    )
    (net (code "94") (name "/PCIE5_LED_WLAN_LS") (class "Default")
      (node (ref "IC23") (pin "3") (pinfunction "A1_3") (pintype "bidirectional"))
    )
    (net (code "95") (name "/PCIE5_LED_WPAN") (class "Default")
      (node (ref "IC31") (pin "20") (pinfunction "B2_20") (pintype "bidirectional"))
    )
    (net (code "96") (name "/PCIE5_LED_WPAN_LS") (class "Default")
      (node (ref "IC31") (pin "4") (pinfunction "A2_4") (pintype "bidirectional"))
    )
    (net (code "97") (name "/PCIE5_LED_WWAN") (class "Default")
      (node (ref "IC23") (pin "14") (pinfunction "B8_14") (pintype "bidirectional"))
    )
    (net (code "98") (name "/PCIE5_LED_WWAN_LS") (class "Default")
      (node (ref "IC23") (pin "10") (pinfunction "A8_10") (pintype "bidirectional"))
    )
    (net (code "99") (name "/PCIE5_PERST") (class "Default")
      (node (ref "IC23") (pin "15") (pinfunction "B7_15") (pintype "bidirectional"))
    )
    (net (code "100") (name "/PCIE5_PERST_LS") (class "Default")
      (node (ref "IC23") (pin "9") (pinfunction "A7_9") (pintype "bidirectional"))
    )
    (net (code "101") (name "/PCIE5_UIM8") (class "Default")
      (node (ref "IC31") (pin "15") (pinfunction "B7_15") (pintype "bidirectional"))
    )
    (net (code "102") (name "/PCIE5_UIM8_LS") (class "Default")
      (node (ref "IC31") (pin "9") (pinfunction "A7_9") (pintype "bidirectional"))
    )
    (net (code "103") (name "/PCIE5_W_DISABLE") (class "Default")
      (node (ref "IC23") (pin "16") (pinfunction "B6_16") (pintype "bidirectional"))
    )
    (net (code "104") (name "/PCIE5_W_DISABLE_LS") (class "Default")
      (node (ref "IC23") (pin "8") (pinfunction "A6_8") (pintype "bidirectional"))
    )
    (net (code "105") (name "/PCIE6_CLK_REQ") (class "Default")
      (node (ref "IC31") (pin "18") (pinfunction "B4_18") (pintype "bidirectional"))
      (node (ref "R150") (pin "1") (pinfunction "1_1") (pintype "passive"))
    )
    (net (code "106") (name "/PCIE6_CLK_REQ_LS") (class "Default")
      (node (ref "IC31") (pin "6") (pinfunction "A4_6") (pintype "bidirectional"))
    )
    (net (code "107") (name "/PCIE6_COEX1") (class "Default")
      (node (ref "IC24") (pin "17") (pinfunction "B5_17") (pintype "bidirectional"))
    )
    (net (code "108") (name "/PCIE6_COEX1_LS") (class "Default")
      (node (ref "IC24") (pin "7") (pinfunction "A5_7") (pintype "bidirectional"))
    )
    (net (code "109") (name "/PCIE6_COEX2") (class "Default")
      (node (ref "IC31") (pin "21") (pinfunction "B1_21") (pintype "bidirectional"))
    )
    (net (code "110") (name "/PCIE6_COEX2_LS") (class "Default")
      (node (ref "IC31") (pin "3") (pinfunction "A1_3") (pintype "bidirectional"))
    )
    (net (code "111") (name "/PCIE6_LED_WLAN") (class "Default")
      (node (ref "IC24") (pin "14") (pinfunction "B8_14") (pintype "bidirectional"))
    )
    (net (code "112") (name "/PCIE6_LED_WLAN_LS") (class "Default")
      (node (ref "IC24") (pin "10") (pinfunction "A8_10") (pintype "bidirectional"))
    )
    (net (code "113") (name "/PCIE6_LED_WPAN") (class "Default")
      (node (ref "IC31") (pin "16") (pinfunction "B6_16") (pintype "bidirectional"))
    )
    (net (code "114") (name "/PCIE6_LED_WPAN_LS") (class "Default")
      (node (ref "IC31") (pin "8") (pinfunction "A6_8") (pintype "bidirectional"))
    )
    (net (code "115") (name "/PCIE6_LED_WWAN") (class "Default")
      (node (ref "IC24") (pin "19") (pinfunction "B3_19") (pintype "bidirectional"))
    )
    (net (code "116") (name "/PCIE6_LED_WWAN_LS") (class "Default")
      (node (ref "IC24") (pin "5") (pinfunction "A3_5") (pintype "bidirectional"))
    )
    (net (code "117") (name "/PCIE6_PERST") (class "Default")
      (node (ref "IC24") (pin "15") (pinfunction "B7_15") (pintype "bidirectional"))
    )
    (net (code "118") (name "/PCIE6_PERST_LS") (class "Default")
      (node (ref "IC24") (pin "9") (pinfunction "A7_9") (pintype "bidirectional"))
    )
    (net (code "119") (name "/PCIE6_UIM8") (class "Default")
      (node (ref "IC31") (pin "17") (pinfunction "B5_17") (pintype "bidirectional"))
    )
    (net (code "120") (name "/PCIE6_UIM8_LS") (class "Default")
      (node (ref "IC31") (pin "7") (pinfunction "A5_7") (pintype "bidirectional"))
    )
    (net (code "121") (name "/PCIE6_W_DISABLE") (class "Default")
      (node (ref "IC24") (pin "20") (pinfunction "B2_20") (pintype "bidirectional"))
    )
    (net (code "122") (name "/PCIE6_W_DISABLE_LS") (class "Default")
      (node (ref "IC24") (pin "4") (pinfunction "A2_4") (pintype "bidirectional"))
    )
    (net (code "123") (name "/PCIE7_CLK_REQ") (class "Default")
      (node (ref "IC33") (pin "15") (pinfunction "B7_15") (pintype "bidirectional"))
      (node (ref "R151") (pin "1") (pinfunction "1_1") (pintype "passive"))
    )
    (net (code "124") (name "/PCIE7_CLK_REQ_LS") (class "Default")
      (node (ref "IC33") (pin "9") (pinfunction "A7_9") (pintype "bidirectional"))
    )
    (net (code "125") (name "/PCIE7_COEX1") (class "Default")
      (node (ref "IC24") (pin "16") (pinfunction "B6_16") (pintype "bidirectional"))
    )
    (net (code "126") (name "/PCIE7_COEX1_LS") (class "Default")
      (node (ref "IC24") (pin "8") (pinfunction "A6_8") (pintype "bidirectional"))
    )
    (net (code "127") (name "/PCIE7_COEX2") (class "Default")
      (node (ref "IC33") (pin "16") (pinfunction "B6_16") (pintype "bidirectional"))
    )
    (net (code "128") (name "/PCIE7_COEX2_LS") (class "Default")
      (node (ref "IC33") (pin "8") (pinfunction "A6_8") (pintype "bidirectional"))
    )
    (net (code "129") (name "/PCIE7_LED_WLAN") (class "Default")
      (node (ref "IC32") (pin "21") (pinfunction "B1_21") (pintype "bidirectional"))
    )
    (net (code "130") (name "/PCIE7_LED_WLAN_LS") (class "Default")
      (node (ref "IC32") (pin "3") (pinfunction "A1_3") (pintype "bidirectional"))
    )
    (net (code "131") (name "/PCIE7_LED_WPAN") (class "Default")
      (node (ref "IC33") (pin "17") (pinfunction "B5_17") (pintype "bidirectional"))
    )
    (net (code "132") (name "/PCIE7_LED_WPAN_LS") (class "Default")
      (node (ref "IC33") (pin "7") (pinfunction "A5_7") (pintype "bidirectional"))
    )
    (net (code "133") (name "/PCIE7_LED_WWAN") (class "Default")
      (node (ref "IC32") (pin "17") (pinfunction "B5_17") (pintype "bidirectional"))
    )
    (net (code "134") (name "/PCIE7_LED_WWAN_LS") (class "Default")
      (node (ref "IC32") (pin "7") (pinfunction "A5_7") (pintype "bidirectional"))
    )
    (net (code "135") (name "/PCIE7_PERST") (class "Default")
      (node (ref "IC32") (pin "14") (pinfunction "B8_14") (pintype "bidirectional"))
    )
    (net (code "136") (name "/PCIE7_PERST_LS") (class "Default")
      (node (ref "IC32") (pin "10") (pinfunction "A8_10") (pintype "bidirectional"))
    )
    (net (code "137") (name "/PCIE7_UIM8") (class "Default")
      (node (ref "IC33") (pin "14") (pinfunction "B8_14") (pintype "bidirectional"))
    )
    (net (code "138") (name "/PCIE7_UIM8_LS") (class "Default")
      (node (ref "IC33") (pin "10") (pinfunction "A8_10") (pintype "bidirectional"))
    )
    (net (code "139") (name "/PCIE7_W_DISABLE") (class "Default")
      (node (ref "IC24") (pin "18") (pinfunction "B4_18") (pintype "bidirectional"))
    )
    (net (code "140") (name "/PCIE7_W_DISABLE_LS") (class "Default")
      (node (ref "IC24") (pin "6") (pinfunction "A4_6") (pintype "bidirectional"))
    )
    (net (code "141") (name "/PCIE8_CLK_REQ") (class "Default")
      (node (ref "IC33") (pin "18") (pinfunction "B4_18") (pintype "bidirectional"))
      (node (ref "R158") (pin "1") (pinfunction "1_1") (pintype "passive"))
    )
    (net (code "142") (name "/PCIE8_CLK_REQ_LS") (class "Default")
      (node (ref "IC33") (pin "6") (pinfunction "A4_6") (pintype "bidirectional"))
    )
    (net (code "143") (name "/PCIE8_COEX1") (class "Default")
      (node (ref "IC32") (pin "16") (pinfunction "B6_16") (pintype "bidirectional"))
    )
    (net (code "144") (name "/PCIE8_COEX1_LS") (class "Default")
      (node (ref "IC32") (pin "8") (pinfunction "A6_8") (pintype "bidirectional"))
    )
    (net (code "145") (name "/PCIE8_COEX2") (class "Default")
      (node (ref "IC33") (pin "19") (pinfunction "B3_19") (pintype "bidirectional"))
    )
    (net (code "146") (name "/PCIE8_COEX2_LS") (class "Default")
      (node (ref "IC33") (pin "5") (pinfunction "A3_5") (pintype "bidirectional"))
    )
    (net (code "147") (name "/PCIE8_LED_WLAN") (class "Default")
      (node (ref "IC28") (pin "16") (pinfunction "B6_16") (pintype "bidirectional"))
    )
    (net (code "148") (name "/PCIE8_LED_WLAN_LS") (class "Default")
      (node (ref "IC28") (pin "8") (pinfunction "A6_8") (pintype "bidirectional"))
    )
    (net (code "149") (name "/PCIE8_LED_WPAN") (class "Default")
      (node (ref "IC33") (pin "20") (pinfunction "B2_20") (pintype "bidirectional"))
    )
    (net (code "150") (name "/PCIE8_LED_WPAN_LS") (class "Default")
      (node (ref "IC33") (pin "4") (pinfunction "A2_4") (pintype "bidirectional"))
    )
    (net (code "151") (name "/PCIE8_LED_WWAN") (class "Default")
      (node (ref "IC32") (pin "20") (pinfunction "B2_20") (pintype "bidirectional"))
    )
    (net (code "152") (name "/PCIE8_LED_WWAN_LS") (class "Default")
      (node (ref "IC32") (pin "4") (pinfunction "A2_4") (pintype "bidirectional"))
    )
    (net (code "153") (name "/PCIE8_PERST") (class "Default")
      (node (ref "IC32") (pin "18") (pinfunction "B4_18") (pintype "bidirectional"))
    )
    (net (code "154") (name "/PCIE8_PERST_LS") (class "Default")
      (node (ref "IC32") (pin "6") (pinfunction "A4_6") (pintype "bidirectional"))
    )
    (net (code "155") (name "/PCIE8_UIM8") (class "Default")
      (node (ref "IC33") (pin "21") (pinfunction "B1_21") (pintype "bidirectional"))
    )
    (net (code "156") (name "/PCIE8_UIM8_LS") (class "Default")
      (node (ref "IC33") (pin "3") (pinfunction "A1_3") (pintype "bidirectional"))
    )
    (net (code "157") (name "/PCIE8_W_DISABLE") (class "Default")
      (node (ref "IC32") (pin "19") (pinfunction "B3_19") (pintype "bidirectional"))
    )
    (net (code "158") (name "/PCIE8_W_DISABLE_LS") (class "Default")
      (node (ref "IC32") (pin "5") (pinfunction "A3_5") (pintype "bidirectional"))
    )
    (net (code "159") (name "/PCIE_SMB_CLK") (class "Default")
      (node (ref "IC26") (pin "17") (pinfunction "B5_17") (pintype "bidirectional"))
    )
    (net (code "160") (name "/PCIE_SMB_CLK_LS") (class "Default")
      (node (ref "IC26") (pin "7") (pinfunction "A5_7") (pintype "bidirectional"))
    )
    (net (code "161") (name "/PCIE_SMB_DATA") (class "Default")
      (node (ref "IC32") (pin "15") (pinfunction "B7_15") (pintype "bidirectional"))
    )
    (net (code "162") (name "/PCIE_SMB_DATA_LS") (class "Default")
      (node (ref "IC32") (pin "9") (pinfunction "A7_9") (pintype "bidirectional"))
    )
    (net (code "163") (name "FMC_HPC_VADJ") (class "Default")
      (node (ref "C167") (pin "2") (pinfunction "2_2") (pintype "passive"))
      (node (ref "C168") (pin "2") (pinfunction "2_2") (pintype "passive"))
      (node (ref "C169") (pin "2") (pinfunction "2_2") (pintype "passive"))
      (node (ref "C170") (pin "2") (pinfunction "2_2") (pintype "passive"))
      (node (ref "C175") (pin "2") (pinfunction "2_2") (pintype "passive"))
      (node (ref "C176") (pin "2") (pinfunction "2_2") (pintype "passive"))
      (node (ref "C177") (pin "2") (pinfunction "2_2") (pintype "passive"))
      (node (ref "C181") (pin "2") (pinfunction "2_2") (pintype "passive"))
      (node (ref "C182") (pin "2") (pinfunction "2_2") (pintype "passive"))
      (node (ref "C186") (pin "2") (pinfunction "2_2") (pintype "passive"))
      (node (ref "C187") (pin "2") (pinfunction "2_2") (pintype "passive"))
      (node (ref "IC23") (pin "1") (pinfunction "VCCA_1") (pintype "power_in"))
      (node (ref "IC24") (pin "1") (pinfunction "VCCA_1") (pintype "power_in"))
      (node (ref "IC25") (pin "1") (pinfunction "VCCA_1") (pintype "power_in"))
      (node (ref "IC26") (pin "1") (pinfunction "VCCA_1") (pintype "power_in"))
      (node (ref "IC27") (pin "1") (pinfunction "VCCA_1") (pintype "power_in"))
      (node (ref "IC28") (pin "1") (pinfunction "VCCA_1") (pintype "power_in"))
      (node (ref "IC29") (pin "1") (pinfunction "VCCA_1") (pintype "power_in"))
      (node (ref "IC30") (pin "1") (pinfunction "VCCA_1") (pintype "power_in"))
      (node (ref "IC31") (pin "1") (pinfunction "VCCA_1") (pintype "power_in"))
      (node (ref "IC32") (pin "1") (pinfunction "VCCA_1") (pintype "power_in"))
      (node (ref "IC33") (pin "1") (pinfunction "VCCA_1") (pintype "power_in"))
      (node (ref "J144") (pin "3") (pinfunction "3_3") (pintype "passive"))
      (node (ref "R132") (pin "1") (pinfunction "1_1") (pintype "passive"))
      (node (ref "R133") (pin "1") (pinfunction "1_1") (pintype "passive"))
      (node (ref "R134") (pin "1") (pinfunction "1_1") (pintype "passive"))
      (node (ref "R135") (pin "1") (pinfunction "1_1") (pintype "passive"))
      (node (ref "R143") (pin "1") (pinfunction "1_1") (pintype "passive"))
      (node (ref "R144") (pin "1") (pinfunction "1_1") (pintype "passive"))
      (node (ref "R145") (pin "1") (pinfunction "1_1") (pintype "passive"))
      (node (ref "R152") (pin "1") (pinfunction "1_1") (pintype "passive"))
      (node (ref "R153") (pin "1") (pinfunction "1_1") (pintype "passive"))
      (node (ref "R154") (pin "1") (pinfunction "1_1") (pintype "passive"))
      (node (ref "R159") (pin "1") (pinfunction "1_1") (pintype "passive"))
      (node (ref "R161") (pin "1") (pinfunction "1_1") (pintype "passive"))
      (node (ref "R162") (pin "1") (pinfunction "1_1") (pintype "passive"))
      (node (ref "VT1") (pin "G") (pinfunction "G_G") (pintype "passive"))
      (node (ref "VT2") (pin "G") (pinfunction "G_G") (pintype "passive"))
    )
    (net (code "164") (name "GND") (class "Default")
      (node (ref "C167") (pin "1") (pinfunction "1_1") (pintype "passive"))
      (node (ref "C168") (pin "1") (pinfunction "1_1") (pintype "passive"))
      (node (ref "C169") (pin "1") (pinfunction "1_1") (pintype "passive"))
      (node (ref "C170") (pin "1") (pinfunction "1_1") (pintype "passive"))
      (node (ref "C171") (pin "1") (pinfunction "1_1") (pintype "passive"))
      (node (ref "C172") (pin "1") (pinfunction "1_1") (pintype "passive"))
      (node (ref "C173") (pin "1") (pinfunction "1_1") (pintype "passive"))
      (node (ref "C174") (pin "1") (pinfunction "1_1") (pintype "passive"))
      (node (ref "C175") (pin "1") (pinfunction "1_1") (pintype "passive"))
      (node (ref "C176") (pin "1") (pinfunction "1_1") (pintype "passive"))
      (node (ref "C177") (pin "1") (pinfunction "1_1") (pintype "passive"))
      (node (ref "C178") (pin "1") (pinfunction "1_1") (pintype "passive"))
      (node (ref "C179") (pin "1") (pinfunction "1_1") (pintype "passive"))
      (node (ref "C180") (pin "1") (pinfunction "1_1") (pintype "passive"))
      (node (ref "C181") (pin "1") (pinfunction "1_1") (pintype "passive"))
      (node (ref "C182") (pin "1") (pinfunction "1_1") (pintype "passive"))
      (node (ref "C183") (pin "1") (pinfunction "1_1") (pintype "passive"))
      (node (ref "C184") (pin "1") (pinfunction "1_1") (pintype "passive"))
      (node (ref "C186") (pin "1") (pinfunction "1_1") (pintype "passive"))
      (node (ref "C187") (pin "1") (pinfunction "1_1") (pintype "passive"))
      (node (ref "C188") (pin "1") (pinfunction "1_1") (pintype "passive"))
      (node (ref "C189") (pin "1") (pinfunction "1_1") (pintype "passive"))
      (node (ref "IC23") (pin "11") (pinfunction "GND_11") (pintype "passive"))
      (node (ref "IC23") (pin "12") (pinfunction "GND_12") (pintype "passive"))
      (node (ref "IC23") (pin "13") (pinfunction "GND_13") (pintype "passive"))
      (node (ref "IC23") (pin "22") (pinfunction "~{OE}_22") (pintype "input"))
      (node (ref "IC23") (pin "PAD") (pinfunction "GND_PAD") (pintype "passive"))
      (node (ref "IC24") (pin "11") (pinfunction "GND_11") (pintype "passive"))
      (node (ref "IC24") (pin "12") (pinfunction "GND_12") (pintype "passive"))
      (node (ref "IC24") (pin "13") (pinfunction "GND_13") (pintype "passive"))
      (node (ref "IC24") (pin "22") (pinfunction "~{OE}_22") (pintype "input"))
      (node (ref "IC24") (pin "PAD") (pinfunction "GND_PAD") (pintype "passive"))
      (node (ref "IC25") (pin "11") (pinfunction "GND_11") (pintype "passive"))
      (node (ref "IC25") (pin "12") (pinfunction "GND_12") (pintype "passive"))
      (node (ref "IC25") (pin "13") (pinfunction "GND_13") (pintype "passive"))
      (node (ref "IC25") (pin "22") (pinfunction "~{OE}_22") (pintype "input"))
      (node (ref "IC25") (pin "PAD") (pinfunction "GND_PAD") (pintype "passive"))
      (node (ref "IC26") (pin "11") (pinfunction "GND_11") (pintype "passive"))
      (node (ref "IC26") (pin "12") (pinfunction "GND_12") (pintype "passive"))
      (node (ref "IC26") (pin "13") (pinfunction "GND_13") (pintype "passive"))
      (node (ref "IC26") (pin "22") (pinfunction "~{OE}_22") (pintype "input"))
      (node (ref "IC26") (pin "PAD") (pinfunction "GND_PAD") (pintype "passive"))
      (node (ref "IC27") (pin "11") (pinfunction "GND_11") (pintype "passive"))
      (node (ref "IC27") (pin "12") (pinfunction "GND_12") (pintype "passive"))
      (node (ref "IC27") (pin "13") (pinfunction "GND_13") (pintype "passive"))
      (node (ref "IC27") (pin "22") (pinfunction "~{OE}_22") (pintype "input"))
      (node (ref "IC27") (pin "PAD") (pinfunction "GND_PAD") (pintype "passive"))
      (node (ref "IC28") (pin "11") (pinfunction "GND_11") (pintype "passive"))
      (node (ref "IC28") (pin "12") (pinfunction "GND_12") (pintype "passive"))
      (node (ref "IC28") (pin "13") (pinfunction "GND_13") (pintype "passive"))
      (node (ref "IC28") (pin "22") (pinfunction "~{OE}_22") (pintype "input"))
      (node (ref "IC28") (pin "PAD") (pinfunction "GND_PAD") (pintype "passive"))
      (node (ref "IC29") (pin "11") (pinfunction "GND_11") (pintype "passive"))
      (node (ref "IC29") (pin "12") (pinfunction "GND_12") (pintype "passive"))
      (node (ref "IC29") (pin "13") (pinfunction "GND_13") (pintype "passive"))
      (node (ref "IC29") (pin "22") (pinfunction "~{OE}_22") (pintype "input"))
      (node (ref "IC29") (pin "PAD") (pinfunction "GND_PAD") (pintype "passive"))
      (node (ref "IC30") (pin "11") (pinfunction "GND_11") (pintype "passive"))
      (node (ref "IC30") (pin "12") (pinfunction "GND_12") (pintype "passive"))
      (node (ref "IC30") (pin "13") (pinfunction "GND_13") (pintype "passive"))
      (node (ref "IC30") (pin "22") (pinfunction "~{OE}_22") (pintype "input"))
      (node (ref "IC30") (pin "PAD") (pinfunction "GND_PAD") (pintype "passive"))
      (node (ref "IC31") (pin "11") (pinfunction "GND_11") (pintype "passive"))
      (node (ref "IC31") (pin "12") (pinfunction "GND_12") (pintype "passive"))
      (node (ref "IC31") (pin "13") (pinfunction "GND_13") (pintype "passive"))
      (node (ref "IC31") (pin "22") (pinfunction "~{OE}_22") (pintype "input"))
      (node (ref "IC31") (pin "PAD") (pinfunction "GND_PAD") (pintype "passive"))
      (node (ref "IC32") (pin "11") (pinfunction "GND_11") (pintype "passive"))
      (node (ref "IC32") (pin "12") (pinfunction "GND_12") (pintype "passive"))
      (node (ref "IC32") (pin "13") (pinfunction "GND_13") (pintype "passive"))
      (node (ref "IC32") (pin "22") (pinfunction "~{OE}_22") (pintype "input"))
      (node (ref "IC32") (pin "PAD") (pinfunction "GND_PAD") (pintype "passive"))
      (node (ref "IC33") (pin "11") (pinfunction "GND_11") (pintype "passive"))
      (node (ref "IC33") (pin "12") (pinfunction "GND_12") (pintype "passive"))
      (node (ref "IC33") (pin "13") (pinfunction "GND_13") (pintype "passive"))
      (node (ref "IC33") (pin "22") (pinfunction "~{OE}_22") (pintype "input"))
      (node (ref "IC33") (pin "PAD") (pinfunction "GND_PAD") (pintype "passive"))
      (node (ref "J144") (pin "1") (pinfunction "1_1") (pintype "passive"))
      (node (ref "J144") (pin "2") (pinfunction "2_2") (pintype "passive"))
      (node (ref "R136") (pin "1") (pinfunction "1_1") (pintype "passive"))
      (node (ref "R137") (pin "1") (pinfunction "1_1") (pintype "passive"))
      (node (ref "R138") (pin "1") (pinfunction "1_1") (pintype "passive"))
      (node (ref "R139") (pin "1") (pinfunction "1_1") (pintype "passive"))
      (node (ref "R146") (pin "1") (pinfunction "1_1") (pintype "passive"))
      (node (ref "R147") (pin "1") (pinfunction "1_1") (pintype "passive"))
      (node (ref "R148") (pin "1") (pinfunction "1_1") (pintype "passive"))
      (node (ref "R156") (pin "1") (pinfunction "1_1") (pintype "passive"))
      (node (ref "R157") (pin "1") (pinfunction "1_1") (pintype "passive"))
      (node (ref "R163") (pin "1") (pinfunction "1_1") (pintype "passive"))
      (node (ref "R164") (pin "1") (pinfunction "1_1") (pintype "passive"))
      (node (ref "R168") (pin "1") (pinfunction "1_1") (pintype "passive"))
      (node (ref "VT3") (pin "S") (pinfunction "S_S") (pintype "passive"))
    )
    (net (code "165") (name "Net-(C185-Pad1)") (class "Default")
      (node (ref "C185") (pin "1") (pinfunction "1_1") (pintype "passive"))
      (node (ref "C200") (pin "1") (pinfunction "1_1") (pintype "passive"))
      (node (ref "J38") (pin "2") (pinfunction "2_2") (pintype "passive"))
      (node (ref "J39") (pin "2") (pinfunction "2_2") (pintype "passive"))
      (node (ref "R165") (pin "2") (pinfunction "2_2") (pintype "passive"))
      (node (ref "R166") (pin "2") (pinfunction "2_2") (pintype "passive"))
      (node (ref "R167") (pin "2") (pinfunction "2_2") (pintype "passive"))
    )
    (net (code "166") (name "Net-(C185-Pad2)") (class "Default")
      (node (ref "C185") (pin "2") (pinfunction "2_2") (pintype "passive"))
      (node (ref "C200") (pin "2") (pinfunction "2_2") (pintype "passive"))
      (node (ref "J38") (pin "1") (pinfunction "1_1") (pintype "passive"))
      (node (ref "J39") (pin "1") (pinfunction "1_1") (pintype "passive"))
      (node (ref "R168") (pin "2") (pinfunction "2_2") (pintype "passive"))
      (node (ref "VT3") (pin "D") (pinfunction "D_D") (pintype "passive"))
    )
    (net (code "167") (name "Net-(IC23-DIR)") (class "Default")
      (node (ref "IC23") (pin "2") (pinfunction "DIR_2") (pintype "input"))
      (node (ref "R132") (pin "2") (pinfunction "2_2") (pintype "passive"))
      (node (ref "R136") (pin "2") (pinfunction "2_2") (pintype "passive"))
    )
    (net (code "168") (name "Net-(IC24-DIR)") (class "Default")
      (node (ref "IC24") (pin "2") (pinfunction "DIR_2") (pintype "input"))
      (node (ref "R133") (pin "2") (pinfunction "2_2") (pintype "passive"))
      (node (ref "R137") (pin "2") (pinfunction "2_2") (pintype "passive"))
    )
    (net (code "169") (name "Net-(IC25-DIR)") (class "Default")
      (node (ref "IC25") (pin "2") (pinfunction "DIR_2") (pintype "input"))
      (node (ref "R134") (pin "2") (pinfunction "2_2") (pintype "passive"))
      (node (ref "R138") (pin "2") (pinfunction "2_2") (pintype "passive"))
    )
    (net (code "170") (name "Net-(IC26-DIR)") (class "Default")
      (node (ref "IC26") (pin "2") (pinfunction "DIR_2") (pintype "input"))
      (node (ref "R135") (pin "2") (pinfunction "2_2") (pintype "passive"))
      (node (ref "R139") (pin "2") (pinfunction "2_2") (pintype "passive"))
    )
    (net (code "171") (name "Net-(IC27-DIR)") (class "Default")
      (node (ref "IC27") (pin "2") (pinfunction "DIR_2") (pintype "input"))
      (node (ref "R143") (pin "2") (pinfunction "2_2") (pintype "passive"))
      (node (ref "R146") (pin "2") (pinfunction "2_2") (pintype "passive"))
    )
    (net (code "172") (name "Net-(IC28-DIR)") (class "Default")
      (node (ref "IC28") (pin "2") (pinfunction "DIR_2") (pintype "input"))
      (node (ref "R144") (pin "2") (pinfunction "2_2") (pintype "passive"))
      (node (ref "R147") (pin "2") (pinfunction "2_2") (pintype "passive"))
    )
    (net (code "173") (name "Net-(IC29-DIR)") (class "Default")
      (node (ref "IC29") (pin "2") (pinfunction "DIR_2") (pintype "input"))
      (node (ref "R145") (pin "2") (pinfunction "2_2") (pintype "passive"))
      (node (ref "R148") (pin "2") (pinfunction "2_2") (pintype "passive"))
    )
    (net (code "174") (name "Net-(IC30-DIR)") (class "Default")
      (node (ref "IC30") (pin "2") (pinfunction "DIR_2") (pintype "input"))
      (node (ref "R152") (pin "2") (pinfunction "2_2") (pintype "passive"))
      (node (ref "R156") (pin "2") (pinfunction "2_2") (pintype "passive"))
    )
    (net (code "175") (name "Net-(IC31-DIR)") (class "Default")
      (node (ref "IC31") (pin "2") (pinfunction "DIR_2") (pintype "input"))
      (node (ref "R153") (pin "2") (pinfunction "2_2") (pintype "passive"))
      (node (ref "R157") (pin "2") (pinfunction "2_2") (pintype "passive"))
    )
    (net (code "176") (name "Net-(IC32-DIR)") (class "Default")
      (node (ref "IC32") (pin "2") (pinfunction "DIR_2") (pintype "input"))
      (node (ref "R161") (pin "2") (pinfunction "2_2") (pintype "passive"))
      (node (ref "R163") (pin "2") (pinfunction "2_2") (pintype "passive"))
    )
    (net (code "177") (name "Net-(IC33-DIR)") (class "Default")
      (node (ref "IC33") (pin "2") (pinfunction "DIR_2") (pintype "input"))
      (node (ref "R162") (pin "2") (pinfunction "2_2") (pintype "passive"))
      (node (ref "R164") (pin "2") (pinfunction "2_2") (pintype "passive"))
    )
    (net (code "178") (name "Net-(R169-Pad2)") (class "Default")
      (node (ref "R169") (pin "2") (pinfunction "2_2") (pintype "passive"))
      (node (ref "VT3") (pin "G") (pinfunction "G_G") (pintype "passive"))
    )
    (net (code "179") (name "VCC3P3_1") (class "Default")
      (node (ref "C171") (pin "2") (pinfunction "2_2") (pintype "passive"))
      (node (ref "C172") (pin "2") (pinfunction "2_2") (pintype "passive"))
      (node (ref "C173") (pin "2") (pinfunction "2_2") (pintype "passive"))
      (node (ref "C174") (pin "2") (pinfunction "2_2") (pintype "passive"))
      (node (ref "C178") (pin "2") (pinfunction "2_2") (pintype "passive"))
      (node (ref "C179") (pin "2") (pinfunction "2_2") (pintype "passive"))
      (node (ref "C180") (pin "2") (pinfunction "2_2") (pintype "passive"))
      (node (ref "C183") (pin "2") (pinfunction "2_2") (pintype "passive"))
      (node (ref "C184") (pin "2") (pinfunction "2_2") (pintype "passive"))
      (node (ref "C188") (pin "2") (pinfunction "2_2") (pintype "passive"))
      (node (ref "C189") (pin "2") (pinfunction "2_2") (pintype "passive"))
      (node (ref "IC23") (pin "23") (pinfunction "VCCB_23") (pintype "power_in"))
      (node (ref "IC23") (pin "24") (pinfunction "VCCB_24") (pintype "power_in"))
      (node (ref "IC24") (pin "23") (pinfunction "VCCB_23") (pintype "power_in"))
      (node (ref "IC24") (pin "24") (pinfunction "VCCB_24") (pintype "power_in"))
      (node (ref "IC25") (pin "23") (pinfunction "VCCB_23") (pintype "power_in"))
      (node (ref "IC25") (pin "24") (pinfunction "VCCB_24") (pintype "power_in"))
      (node (ref "IC26") (pin "23") (pinfunction "VCCB_23") (pintype "power_in"))
      (node (ref "IC26") (pin "24") (pinfunction "VCCB_24") (pintype "power_in"))
      (node (ref "IC27") (pin "23") (pinfunction "VCCB_23") (pintype "power_in"))
      (node (ref "IC27") (pin "24") (pinfunction "VCCB_24") (pintype "power_in"))
      (node (ref "IC28") (pin "23") (pinfunction "VCCB_23") (pintype "power_in"))
      (node (ref "IC28") (pin "24") (pinfunction "VCCB_24") (pintype "power_in"))
      (node (ref "IC29") (pin "23") (pinfunction "VCCB_23") (pintype "power_in"))
      (node (ref "IC29") (pin "24") (pinfunction "VCCB_24") (pintype "power_in"))
      (node (ref "IC30") (pin "23") (pinfunction "VCCB_23") (pintype "power_in"))
      (node (ref "IC30") (pin "24") (pinfunction "VCCB_24") (pintype "power_in"))
      (node (ref "IC31") (pin "23") (pinfunction "VCCB_23") (pintype "power_in"))
      (node (ref "IC31") (pin "24") (pinfunction "VCCB_24") (pintype "power_in"))
      (node (ref "IC32") (pin "23") (pinfunction "VCCB_23") (pintype "power_in"))
      (node (ref "IC32") (pin "24") (pinfunction "VCCB_24") (pintype "power_in"))
      (node (ref "IC33") (pin "23") (pinfunction "VCCB_23") (pintype "power_in"))
      (node (ref "IC33") (pin "24") (pinfunction "VCCB_24") (pintype "power_in"))
      (node (ref "J144") (pin "4") (pinfunction "4_4") (pintype "passive"))
      (node (ref "R131") (pin "2") (pinfunction "2_2") (pintype "passive"))
      (node (ref "R140") (pin "2") (pinfunction "2_2") (pintype "passive"))
      (node (ref "R141") (pin "2") (pinfunction "2_2") (pintype "passive"))
      (node (ref "R142") (pin "2") (pinfunction "2_2") (pintype "passive"))
      (node (ref "R149") (pin "2") (pinfunction "2_2") (pintype "passive"))
      (node (ref "R150") (pin "2") (pinfunction "2_2") (pintype "passive"))
      (node (ref "R151") (pin "2") (pinfunction "2_2") (pintype "passive"))
      (node (ref "R155") (pin "1") (pinfunction "1_1") (pintype "passive"))
      (node (ref "R158") (pin "2") (pinfunction "2_2") (pintype "passive"))
      (node (ref "R160") (pin "1") (pinfunction "1_1") (pintype "passive"))
    )
    (net (code "180") (name "VCC3P3_2") (class "Default")
      (node (ref "R167") (pin "1") (pinfunction "1_1") (pintype "passive"))
    )
    (net (code "181") (name "VCC5P0") (class "Default")
      (node (ref "R166") (pin "1") (pinfunction "1_1") (pintype "passive"))
    )
    (net (code "182") (name "VCC_INT") (class "Default")
      (node (ref "R165") (pin "1") (pinfunction "1_1") (pintype "passive"))
    )
    (net (code "183") (name "unconnected-(IC26-A1-Pad3)") (class "Default")
      (node (ref "IC26") (pin "3") (pinfunction "A1_3") (pintype "bidirectional+no_connect"))
    )
    (net (code "184") (name "unconnected-(IC26-A2-Pad4)") (class "Default")
      (node (ref "IC26") (pin "4") (pinfunction "A2_4") (pintype "bidirectional+no_connect"))
    )
    (net (code "185") (name "unconnected-(IC26-A3-Pad5)") (class "Default")
      (node (ref "IC26") (pin "5") (pinfunction "A3_5") (pintype "bidirectional+no_connect"))
    )
    (net (code "186") (name "unconnected-(IC26-A6-Pad8)") (class "Default")
      (node (ref "IC26") (pin "8") (pinfunction "A6_8") (pintype "bidirectional+no_connect"))
    )
    (net (code "187") (name "unconnected-(IC26-A7-Pad9)") (class "Default")
      (node (ref "IC26") (pin "9") (pinfunction "A7_9") (pintype "bidirectional+no_connect"))
    )
    (net (code "188") (name "unconnected-(IC26-A8-Pad10)") (class "Default")
      (node (ref "IC26") (pin "10") (pinfunction "A8_10") (pintype "bidirectional+no_connect"))
    )
    (net (code "189") (name "unconnected-(IC26-B1-Pad21)") (class "Default")
      (node (ref "IC26") (pin "21") (pinfunction "B1_21") (pintype "bidirectional+no_connect"))
    )
    (net (code "190") (name "unconnected-(IC26-B2-Pad20)") (class "Default")
      (node (ref "IC26") (pin "20") (pinfunction "B2_20") (pintype "bidirectional+no_connect"))
    )
    (net (code "191") (name "unconnected-(IC26-B3-Pad19)") (class "Default")
      (node (ref "IC26") (pin "19") (pinfunction "B3_19") (pintype "bidirectional"))
    )
    (net (code "192") (name "unconnected-(IC26-B6-Pad16)") (class "Default")
      (node (ref "IC26") (pin "16") (pinfunction "B6_16") (pintype "bidirectional+no_connect"))
    )
    (net (code "193") (name "unconnected-(IC26-B7-Pad15)") (class "Default")
      (node (ref "IC26") (pin "15") (pinfunction "B7_15") (pintype "bidirectional+no_connect"))
    )
    (net (code "194") (name "unconnected-(IC26-B8-Pad14)") (class "Default")
      (node (ref "IC26") (pin "14") (pinfunction "B8_14") (pintype "bidirectional+no_connect"))
    )
    (net (code "195") (name "unconnected-(IC28-A7-Pad9)") (class "Default")
      (node (ref "IC28") (pin "9") (pinfunction "A7_9") (pintype "bidirectional+no_connect"))
    )
    (net (code "196") (name "unconnected-(IC28-A8-Pad10)") (class "Default")
      (node (ref "IC28") (pin "10") (pinfunction "A8_10") (pintype "bidirectional+no_connect"))
    )
    (net (code "197") (name "unconnected-(IC28-B7-Pad15)") (class "Default")
      (node (ref "IC28") (pin "15") (pinfunction "B7_15") (pintype "bidirectional+no_connect"))
    )
    (net (code "198") (name "unconnected-(IC28-B8-Pad14)") (class "Default")
      (node (ref "IC28") (pin "14") (pinfunction "B8_14") (pintype "bidirectional+no_connect"))
    )
  )
)
